# femtoBeacon_PRO_r3_0_2_single_sided.net
KiCad netlist of a schematic drawn in EAGLE
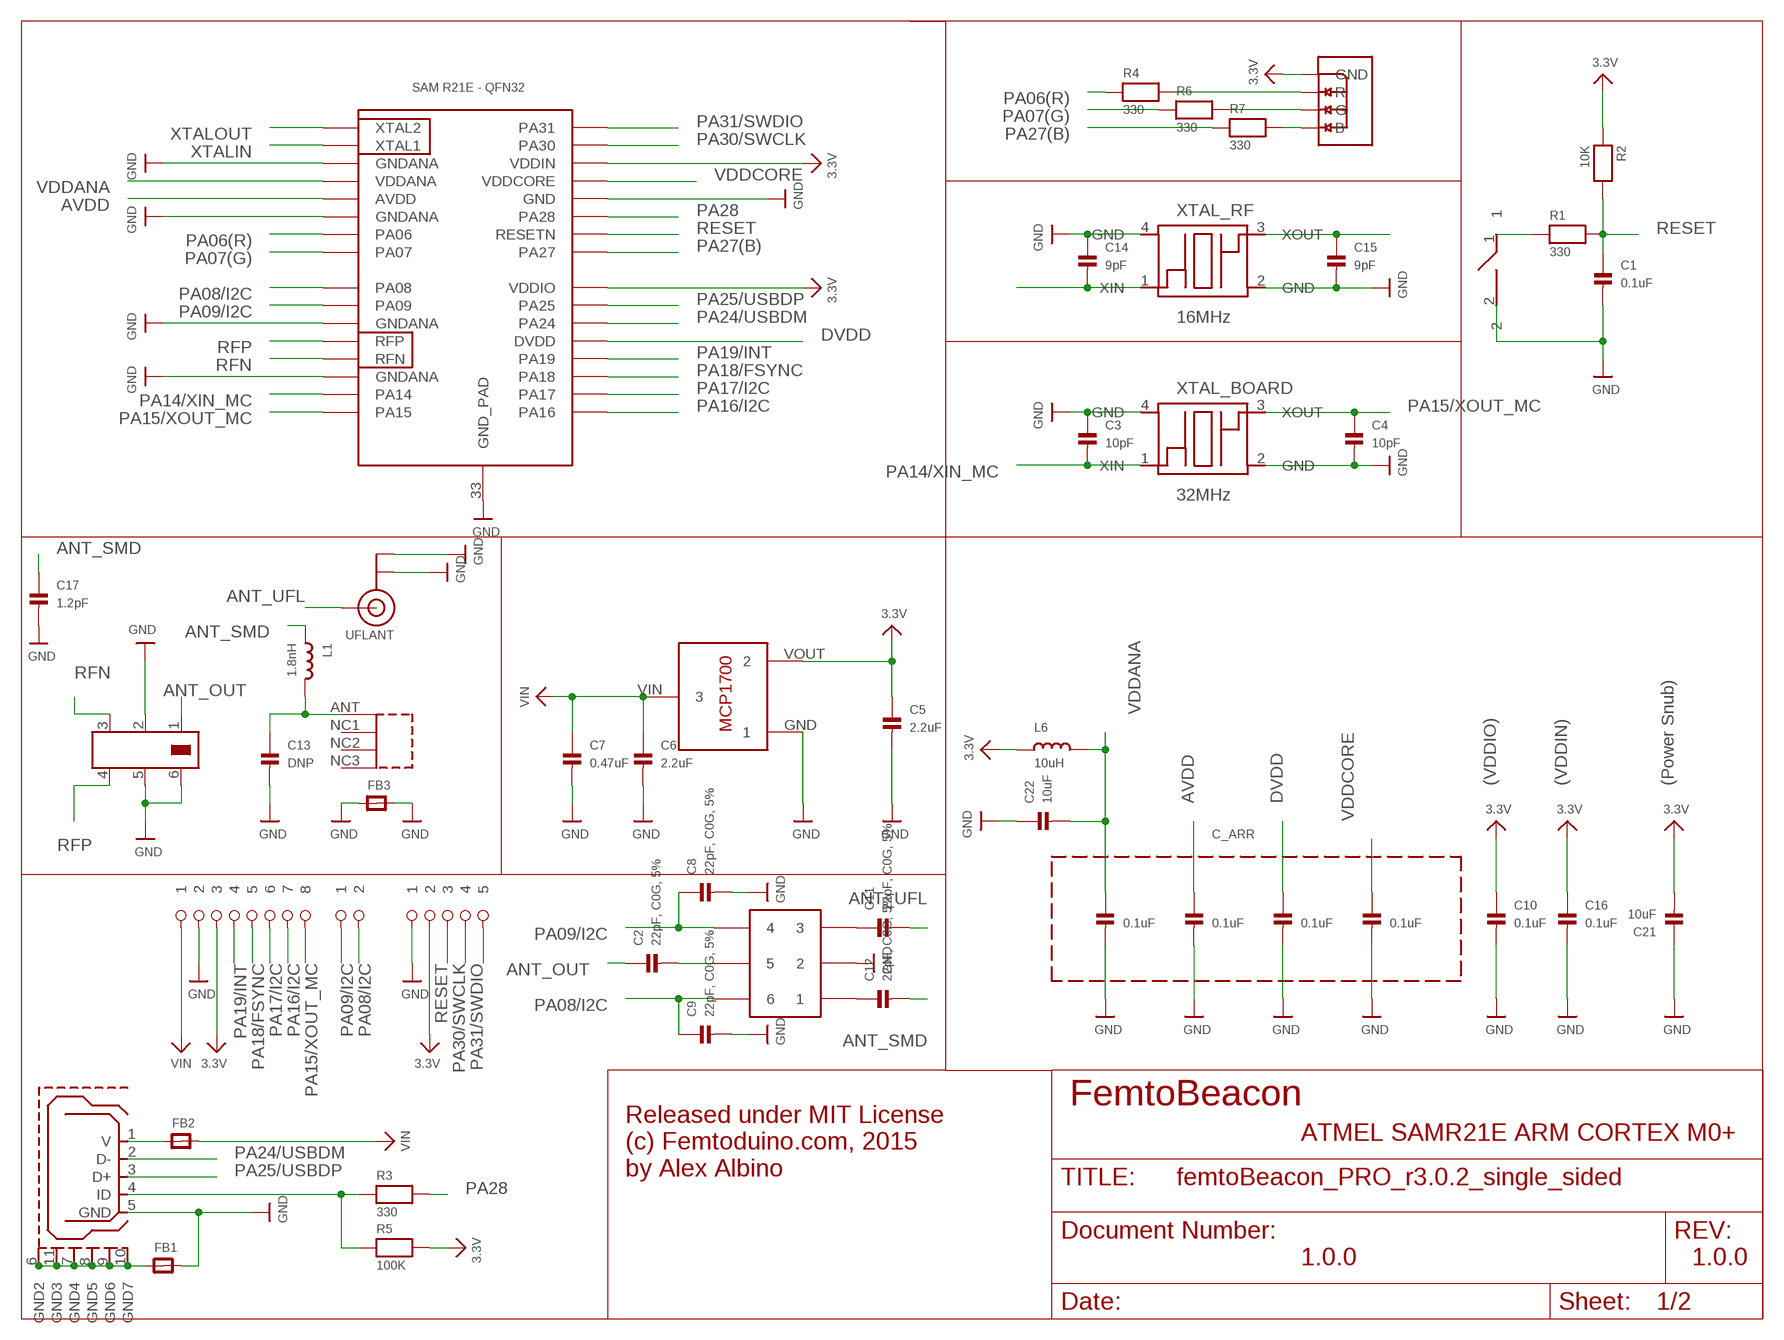
[diagram p0: schematic, sheet 1]
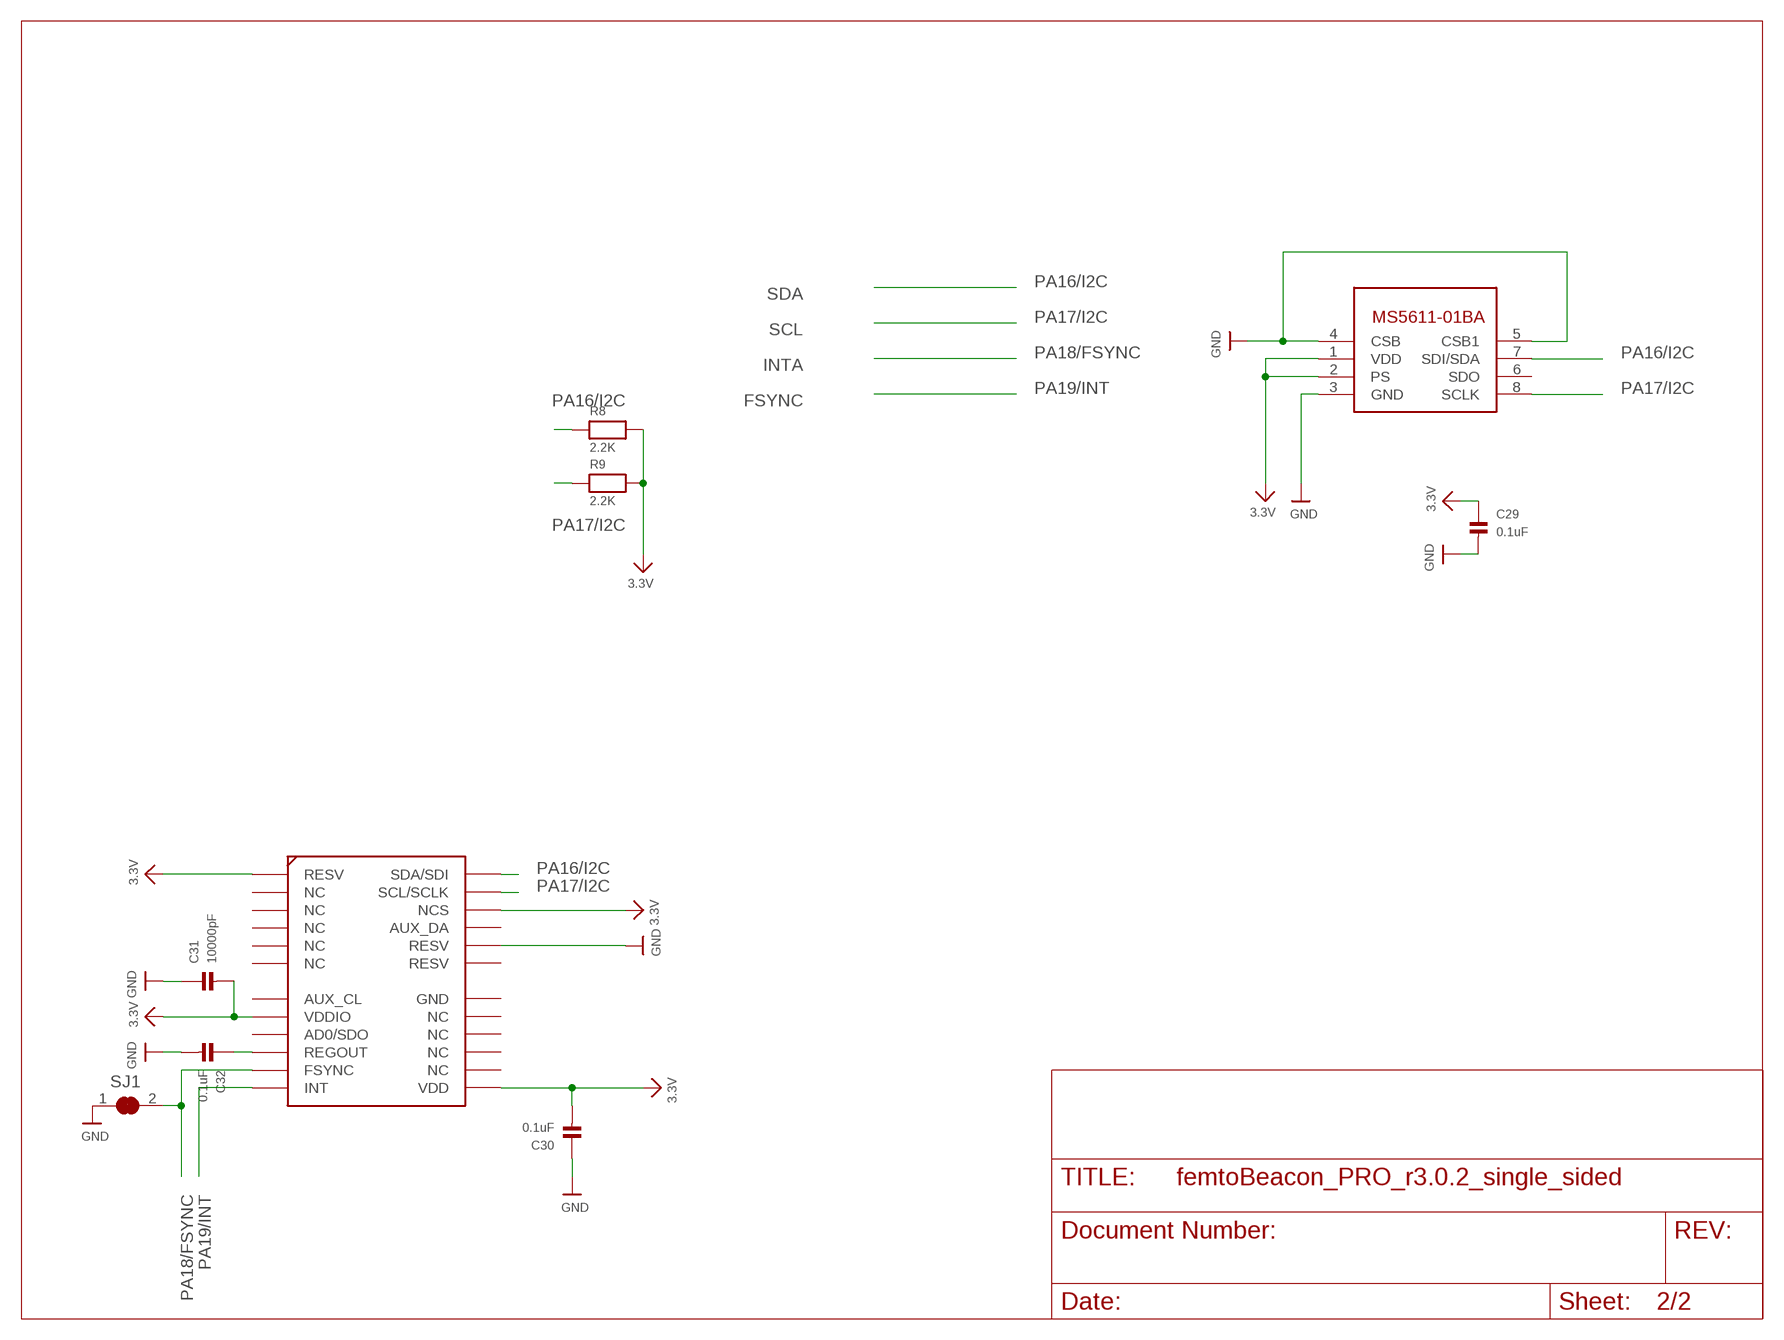
[diagram p1: schematic, sheet 2]

(export (version "E")
  (design (tool "Eeschema 10.0.6"))
  (components
    (comp (ref "ASWITCH")
      (value "AS222-92LF")
      (footprint "eagle-import:AS222-92LF")
      (libsource (lib "eagle-import") (part "AS222-92LF"))
    )
    (comp (ref "BALUN")
      (value "JOHANSON_2450BM15A0015E")
      (footprint "eagle-import:0805_BALUN")
      (libsource (lib "eagle-import") (part "JOHANSON_2450BM15A0015E"))
    )
    (comp (ref "BTN_RESET")
      (value "DNP")
      (footprint "eagle-import:SPST_SMD")
      (libsource (lib "eagle-import") (part "SPST_SMD"))
    )
    (comp (ref "C1")
      (value "0.1uF")
      (footprint "eagle-import:_0402MP")
      (fields (field (name "DIGIKEY_PART") "490-3194-1-ND"))
      (libsource (lib "eagle-import") (part "CAP_CERAMIC_0402MP"))
    )
    (comp (ref "C2")
      (value "22pF, C0G, 5%")
      (footprint "eagle-import:_0402MP")
      (fields (field (name "DIGIKEY_PART") "490-3194-1-ND"))
      (libsource (lib "eagle-import") (part "CAP_CERAMIC_0402MP"))
    )
    (comp (ref "C3")
      (value "10pF")
      (footprint "eagle-import:_0402MP")
      (fields (field (name "DIGIKEY_PART") "490-3194-1-ND"))
      (libsource (lib "eagle-import") (part "CAP_CERAMIC_0402MP"))
    )
    (comp (ref "C4")
      (value "10pF")
      (footprint "eagle-import:_0402MP")
      (fields (field (name "DIGIKEY_PART") "490-3194-1-ND"))
      (libsource (lib "eagle-import") (part "CAP_CERAMIC_0402MP"))
    )
    (comp (ref "C5")
      (value "2.2uF")
      (footprint "eagle-import:_0402MP")
      (libsource (lib "eagle-import") (part "CAP_CERAMIC_0402MP"))
    )
    (comp (ref "C6")
      (value "2.2uF")
      (footprint "eagle-import:_0402MP")
      (libsource (lib "eagle-import") (part "CAP_CERAMIC_0402MP"))
    )
    (comp (ref "C7")
      (value "0.47uF")
      (footprint "eagle-import:_0402MP")
      (libsource (lib "eagle-import") (part "CAP_CERAMIC_0402MP"))
    )
    (comp (ref "C8")
      (value "22pF, C0G, 5%")
      (footprint "eagle-import:_0402MP")
      (fields (field (name "DIGIKEY_PART") "490-3194-1-ND"))
      (libsource (lib "eagle-import") (part "CAP_CERAMIC_0402MP"))
    )
    (comp (ref "C9")
      (value "22pF, C0G, 5%")
      (footprint "eagle-import:_0402MP")
      (fields (field (name "DIGIKEY_PART") "490-3194-1-ND"))
      (libsource (lib "eagle-import") (part "CAP_CERAMIC_0402MP"))
    )
    (comp (ref "C10")
      (value "0.1uF")
      (footprint "eagle-import:_0402MP")
      (fields (field (name "DIGIKEY_PART") "490-3194-1-ND"))
      (libsource (lib "eagle-import") (part "CAP_CERAMIC_0402MP"))
    )
    (comp (ref "C11")
      (value "22pF, C0G, 5%")
      (footprint "eagle-import:_0402MP")
      (fields (field (name "DIGIKEY_PART") "490-3194-1-ND"))
      (libsource (lib "eagle-import") (part "CAP_CERAMIC_0402MP"))
    )
    (comp (ref "C12")
      (value "22pF, C0G, 5%")
      (footprint "eagle-import:_0402MP")
      (fields (field (name "DIGIKEY_PART") "490-3194-1-ND"))
      (libsource (lib "eagle-import") (part "CAP_CERAMIC_0402MP"))
    )
    (comp (ref "C13")
      (value "DNP")
      (footprint "eagle-import:_0402MP")
      (fields (field (name "DIGIKEY_PART") "490-3194-1-ND"))
      (libsource (lib "eagle-import") (part "CAP_CERAMIC_0402MP"))
    )
    (comp (ref "C14")
      (value "9pF")
      (footprint "eagle-import:_0402MP")
      (fields (field (name "DIGIKEY_PART") "490-3194-1-ND"))
      (libsource (lib "eagle-import") (part "CAP_CERAMIC_0402MP"))
    )
    (comp (ref "C15")
      (value "9pF")
      (footprint "eagle-import:_0402MP")
      (fields (field (name "DIGIKEY_PART") "490-3194-1-ND"))
      (libsource (lib "eagle-import") (part "CAP_CERAMIC_0402MP"))
    )
    (comp (ref "C16")
      (value "0.1uF")
      (footprint "eagle-import:_0402MP")
      (fields (field (name "DIGIKEY_PART") "490-3194-1-ND"))
      (libsource (lib "eagle-import") (part "CAP_CERAMIC_0402MP"))
    )
    (comp (ref "C17")
      (value "1.2pF")
      (footprint "eagle-import:_0402MP")
      (libsource (lib "eagle-import") (part "CAP_CERAMIC_0402MP"))
    )
    (comp (ref "C21")
      (value "10uF")
      (footprint "eagle-import:_0402MP")
      (libsource (lib "eagle-import") (part "CAP_CERAMIC_0402MP"))
    )
    (comp (ref "C22")
      (value "10uF")
      (footprint "eagle-import:_0402MP")
      (libsource (lib "eagle-import") (part "CAP_CERAMIC_0402MP"))
    )
    (comp (ref "C_ARR")
      (value "0.1uF")
      (footprint "eagle-import:CAPACITOR_ARRAY_1206_MONO_1X4")
      (libsource (lib "eagle-import") (part "KEMET_CERAMIC_CAPACITOR_ARRAY_1X4"))
    )
    (comp (ref "FB1")
      (value "FERRITE_0603MP")
      (footprint "eagle-import:_0603MP")
      (libsource (lib "eagle-import") (part "FERRITE_0603MP"))
    )
    (comp (ref "FB2")
      (value "FERRITE_0603MP")
      (footprint "eagle-import:_0603MP")
      (libsource (lib "eagle-import") (part "FERRITE_0603MP"))
    )
    (comp (ref "FB3")
      (value "FERRITE_0603MP")
      (footprint "eagle-import:_0603MP")
      (libsource (lib "eagle-import") (part "FERRITE_0603MP"))
    )
    (comp (ref "IC")
      (value "ATSAMR21E18A-MUT")
      (footprint "eagle-import:QFN32")
      (libsource (lib "eagle-import") (part "ATSAMR21E18A-MUT"))
    )
    (comp (ref "L1")
      (value "1.8nH")
      (footprint "eagle-import:_0603MP")
      (libsource (lib "eagle-import") (part "INDUCTOR_0603MP"))
    )
    (comp (ref "L6")
      (value "10uH")
      (footprint "eagle-import:_0603MP")
      (libsource (lib "eagle-import") (part "INDUCTOR_0603MP"))
    )
    (comp (ref "LDO_VREG")
      (value "MCP1700T-3302E/TT")
      (footprint "eagle-import:MCP1700T-3302E_TT")
      (libsource (lib "eagle-import") (part "MCP1700T-3302E/TT"))
    )
    (comp (ref "R1")
      (value "330")
      (footprint "eagle-import:_0402MP")
      (libsource (lib "eagle-import") (part "RESISTOR_0402MP"))
    )
    (comp (ref "R2")
      (value "10K")
      (footprint "eagle-import:_0402MP")
      (libsource (lib "eagle-import") (part "RESISTOR_0402MP"))
    )
    (comp (ref "R3")
      (value "330")
      (footprint "eagle-import:_0402MP")
      (libsource (lib "eagle-import") (part "RESISTOR_0402MP"))
    )
    (comp (ref "R4")
      (value "330")
      (footprint "eagle-import:_0402MP")
      (libsource (lib "eagle-import") (part "RESISTOR_0402MP"))
    )
    (comp (ref "R5")
      (value "100K")
      (footprint "eagle-import:_0402MP")
      (libsource (lib "eagle-import") (part "RESISTOR_0402MP"))
    )
    (comp (ref "R6")
      (value "330")
      (footprint "eagle-import:_0402MP")
      (libsource (lib "eagle-import") (part "RESISTOR_0402MP"))
    )
    (comp (ref "R7")
      (value "330")
      (footprint "eagle-import:_0402MP")
      (libsource (lib "eagle-import") (part "RESISTOR_0402MP"))
    )
    (comp (ref "RGBLED")
      (value "LRTB_R48G")
      (footprint "eagle-import:LRTB_R48G")
      (libsource (lib "eagle-import") (part "LRTB_R48G"))
    )
    (comp (ref "U$5")
      (value "1X8_ROUND")
      (footprint "eagle-import:1X8_ROUND")
      (libsource (lib "eagle-import") (part "1X8_ROUND"))
    )
    (comp (ref "U$9")
      (value "1X2_ROUND")
      (footprint "eagle-import:1X2_ROUND")
      (libsource (lib "eagle-import") (part "1X2_ROUND"))
    )
    (comp (ref "U$10")
      (value "1X5_ROUND")
      (footprint "eagle-import:1X5_ROUND")
      (libsource (lib "eagle-import") (part "1X5_ROUND"))
    )
    (comp (ref "U$12")
      (value "0479480001")
      (footprint "eagle-import:0479480001")
      (libsource (lib "eagle-import") (part "0479480001"))
    )
    (comp (ref "UFLANT")
      (value "ANTENNA_U.FL")
      (footprint "eagle-import:U.FL")
      (libsource (lib "eagle-import") (part "ANTENNA_U.FL"))
    )
    (comp (ref "USB")
      (value "USB_MICROB")
      (footprint "eagle-import:USB_MICROB_PACKAGE")
      (libsource (lib "eagle-import") (part "USB_MICROB"))
    )
    (comp (ref "XTAL_BOARD")
      (value "32MHz")
      (footprint "eagle-import:FA-128")
      (libsource (lib "eagle-import") (part "FA-128"))
    )
    (comp (ref "XTAL_RF")
      (value "16MHz")
      (footprint "eagle-import:TSX-3225")
      (libsource (lib "eagle-import") (part "TSX-3225"))
    )
    (comp (ref "BARO")
      (value "MS5611-01BA03")
      (footprint "eagle-import:MS5611-01BA03")
      (libsource (lib "eagle-import") (part "MS5611-01BA03"))
    )
    (comp (ref "C29")
      (value "0.1uF")
      (footprint "eagle-import:_0402MP")
      (fields (field (name "DIGIKEY_PART") "490-3194-1-ND"))
      (libsource (lib "eagle-import") (part "CAP_CERAMIC_0402MP"))
    )
    (comp (ref "C30")
      (value "0.1uF")
      (footprint "eagle-import:_0402MP")
      (fields (field (name "DIGIKEY_PART") "490-3194-1-ND"))
      (libsource (lib "eagle-import") (part "CAP_CERAMIC_0402MP"))
    )
    (comp (ref "C31")
      (value "10000pF")
      (footprint "eagle-import:_0402MP")
      (fields (field (name "DIGIKEY_PART") "490-3194-1-ND"))
      (libsource (lib "eagle-import") (part "CAP_CERAMIC_0402MP"))
    )
    (comp (ref "C32")
      (value "0.1uF")
      (footprint "eagle-import:_0402MP")
      (fields (field (name "DIGIKEY_PART") "490-3194-1-ND"))
      (libsource (lib "eagle-import") (part "CAP_CERAMIC_0402MP"))
    )
    (comp (ref "IMU")
      (value "MPU-9250")
      (footprint "eagle-import:QFN_3X3MM")
      (libsource (lib "eagle-import") (part "MPU-9250"))
    )
    (comp (ref "R8")
      (value "2.2K")
      (footprint "eagle-import:_0402MP")
      (libsource (lib "eagle-import") (part "RESISTOR_0402MP"))
    )
    (comp (ref "R9")
      (value "2.2K")
      (footprint "eagle-import:_0402MP")
      (libsource (lib "eagle-import") (part "RESISTOR_0402MP"))
    )
    (comp (ref "SJ1")
      (value "SOLDERJUMPER_CLOSED")
      (footprint "eagle-import:SOLDERJUMPER_CLOSEDWIRE")
      (libsource (lib "eagle-import") (part "SOLDERJUMPER_CLOSED"))
    )
  )
  (nets
    (net (code "1") (name "3.3V") (class "Default")
      (node (ref "BARO") (pin "1") (pinfunction "VDD_1") (pintype "bidirectional"))
      (node (ref "BARO") (pin "2") (pinfunction "PS_2") (pintype "bidirectional"))
      (node (ref "C10") (pin "1") (pinfunction "P$1_1") (pintype "passive"))
      (node (ref "C16") (pin "1") (pinfunction "P$1_1") (pintype "passive"))
      (node (ref "C21") (pin "2") (pinfunction "P$2_2") (pintype "passive"))
      (node (ref "C29") (pin "1") (pinfunction "P$1_1") (pintype "passive"))
      (node (ref "C30") (pin "2") (pinfunction "P$2_2") (pintype "passive"))
      (node (ref "C31") (pin "2") (pinfunction "P$2_2") (pintype "passive"))
      (node (ref "C5") (pin "1") (pinfunction "P$1_1") (pintype "passive"))
      (node (ref "IC") (pin "24") (pinfunction "VDDIO_24") (pintype "bidirectional"))
      (node (ref "IC") (pin "30") (pinfunction "VDDIN_30") (pintype "bidirectional"))
      (node (ref "IMU") (pin "P$1") (pinfunction "RESV_P$1") (pintype "bidirectional"))
      (node (ref "IMU") (pin "P$13") (pinfunction "VDD_P$13") (pintype "bidirectional"))
      (node (ref "IMU") (pin "P$22") (pinfunction "NCS_P$22") (pintype "bidirectional"))
      (node (ref "IMU") (pin "P$8") (pinfunction "VDDIO_P$8") (pintype "bidirectional"))
      (node (ref "L6") (pin "1") (pinfunction "1_1") (pintype "passive"))
      (node (ref "LDO_VREG") (pin "VOUT") (pinfunction "2_VOUT") (pintype "bidirectional"))
      (node (ref "R2") (pin "1") (pinfunction "1_1") (pintype "passive"))
      (node (ref "R5") (pin "2") (pinfunction "2_2") (pintype "passive"))
      (node (ref "R8") (pin "2") (pinfunction "2_2") (pintype "passive"))
      (node (ref "R9") (pin "2") (pinfunction "2_2") (pintype "passive"))
      (node (ref "RGBLED") (pin "1") (pinfunction "GND_1") (pintype "bidirectional"))
      (node (ref "U$10") (pin "P$2") (pinfunction "2_P$2") (pintype "bidirectional"))
      (node (ref "U$5") (pin "P$3") (pinfunction "3_P$3") (pintype "bidirectional"))
    )
    (net (code "2") (name "ANT_OUT") (class "Default")
      (node (ref "BALUN") (pin "1") (pinfunction "1_1") (pintype "bidirectional"))
      (node (ref "C2") (pin "1") (pinfunction "P$1_1") (pintype "passive"))
    )
    (net (code "3") (name "ANT_SMD") (class "Default")
      (node (ref "C12") (pin "2") (pinfunction "P$2_2") (pintype "passive"))
      (node (ref "C17") (pin "1") (pinfunction "P$1_1") (pintype "passive"))
      (node (ref "L1") (pin "1") (pinfunction "1_1") (pintype "passive"))
    )
    (net (code "4") (name "ANT_UFL") (class "Default")
      (node (ref "C11") (pin "2") (pinfunction "P$2_2") (pintype "passive"))
      (node (ref "UFLANT") (pin "3") (pinfunction "SIGNAL_3") (pintype "passive"))
    )
    (net (code "5") (name "AVDD") (class "Default")
      (node (ref "C_ARR") (pin "3") (pinfunction "P$3_3") (pintype "passive"))
      (node (ref "IC") (pin "5") (pinfunction "AVDD_5") (pintype "bidirectional"))
    )
    (net (code "6") (name "DVDD") (class "Default")
      (node (ref "C_ARR") (pin "5") (pinfunction "P$5_5") (pintype "passive"))
      (node (ref "IC") (pin "21") (pinfunction "DVDD_21") (pintype "bidirectional"))
    )
    (net (code "7") (name "GND") (class "Default")
      (node (ref "ASWITCH") (pin "PIN2") (pinfunction "2_PIN2") (pintype "bidirectional"))
      (node (ref "BALUN") (pin "2") (pinfunction "2_2") (pintype "bidirectional"))
      (node (ref "BALUN") (pin "5") (pinfunction "5_5") (pintype "bidirectional"))
      (node (ref "BALUN") (pin "6") (pinfunction "6_6") (pintype "bidirectional"))
      (node (ref "BARO") (pin "3") (pinfunction "GND_3") (pintype "bidirectional"))
      (node (ref "BARO") (pin "4") (pinfunction "CSB_4") (pintype "bidirectional"))
      (node (ref "BARO") (pin "5") (pinfunction "CSB1_5") (pintype "bidirectional"))
      (node (ref "BTN_RESET") (pin "2") (pinfunction "2_2") (pintype "bidirectional"))
      (node (ref "C1") (pin "2") (pinfunction "P$2_2") (pintype "passive"))
      (node (ref "C10") (pin "2") (pinfunction "P$2_2") (pintype "passive"))
      (node (ref "C13") (pin "2") (pinfunction "P$2_2") (pintype "passive"))
      (node (ref "C14") (pin "1") (pinfunction "P$1_1") (pintype "passive"))
      (node (ref "C15") (pin "2") (pinfunction "P$2_2") (pintype "passive"))
      (node (ref "C16") (pin "2") (pinfunction "P$2_2") (pintype "passive"))
      (node (ref "C17") (pin "2") (pinfunction "P$2_2") (pintype "passive"))
      (node (ref "C21") (pin "1") (pinfunction "P$1_1") (pintype "passive"))
      (node (ref "C22") (pin "1") (pinfunction "P$1_1") (pintype "passive"))
      (node (ref "C29") (pin "2") (pinfunction "P$2_2") (pintype "passive"))
      (node (ref "C3") (pin "1") (pinfunction "P$1_1") (pintype "passive"))
      (node (ref "C30") (pin "1") (pinfunction "P$1_1") (pintype "passive"))
      (node (ref "C31") (pin "1") (pinfunction "P$1_1") (pintype "passive"))
      (node (ref "C32") (pin "2") (pinfunction "P$2_2") (pintype "passive"))
      (node (ref "C4") (pin "2") (pinfunction "P$2_2") (pintype "passive"))
      (node (ref "C5") (pin "2") (pinfunction "P$2_2") (pintype "passive"))
      (node (ref "C6") (pin "2") (pinfunction "P$2_2") (pintype "passive"))
      (node (ref "C7") (pin "2") (pinfunction "P$2_2") (pintype "passive"))
      (node (ref "C8") (pin "2") (pinfunction "P$2_2") (pintype "passive"))
      (node (ref "C9") (pin "2") (pinfunction "P$2_2") (pintype "passive"))
      (node (ref "C_ARR") (pin "2") (pinfunction "P$2_2") (pintype "passive"))
      (node (ref "C_ARR") (pin "4") (pinfunction "P$4_4") (pintype "passive"))
      (node (ref "C_ARR") (pin "6") (pinfunction "P$6_6") (pintype "passive"))
      (node (ref "C_ARR") (pin "8") (pinfunction "P$8_8") (pintype "passive"))
      (node (ref "FB1") (pin "2") (pinfunction "P$2_2") (pintype "passive"))
      (node (ref "FB3") (pin "1") (pinfunction "P$1_1") (pintype "passive"))
      (node (ref "FB3") (pin "2") (pinfunction "P$2_2") (pintype "passive"))
      (node (ref "IC") (pin "11") (pinfunction "GNDANA_11") (pintype "bidirectional"))
      (node (ref "IC") (pin "14") (pinfunction "GNDANA_14") (pintype "bidirectional"))
      (node (ref "IC") (pin "28") (pinfunction "GND_28") (pintype "bidirectional"))
      (node (ref "IC") (pin "3") (pinfunction "GNDANA_3") (pintype "bidirectional"))
      (node (ref "IC") (pin "33") (pinfunction "GND_PAD_33") (pintype "bidirectional"))
      (node (ref "IC") (pin "6") (pinfunction "GNDANA_6") (pintype "bidirectional"))
      (node (ref "IMU") (pin "P$20") (pinfunction "RESV_P$20") (pintype "bidirectional"))
      (node (ref "LDO_VREG") (pin "GND") (pinfunction "1_GND") (pintype "bidirectional"))
      (node (ref "SJ1") (pin "1") (pinfunction "1_1") (pintype "passive"))
      (node (ref "U$10") (pin "P$1") (pinfunction "1_P$1") (pintype "bidirectional"))
      (node (ref "U$5") (pin "P$2") (pinfunction "2_P$2") (pintype "bidirectional"))
      (node (ref "UFLANT") (pin "1") (pinfunction "GND_1") (pintype "passive"))
      (node (ref "UFLANT") (pin "2") (pinfunction "GND_2") (pintype "passive"))
      (node (ref "USB") (pin "5") (pinfunction "GND_5") (pintype "bidirectional"))
      (node (ref "XTAL_BOARD") (pin "2") (pinfunction "GND_2") (pintype "bidirectional"))
      (node (ref "XTAL_BOARD") (pin "4") (pinfunction "GND_4") (pintype "bidirectional"))
      (node (ref "XTAL_RF") (pin "2") (pinfunction "GND_2") (pintype "bidirectional"))
      (node (ref "XTAL_RF") (pin "4") (pinfunction "GND_4") (pintype "bidirectional"))
    )
    (net (code "8") (name "Net-(ASWITCH-1)") (class "Default")
      (node (ref "ASWITCH") (pin "PIN1") (pinfunction "1_PIN1") (pintype "bidirectional"))
      (node (ref "C12") (pin "1") (pinfunction "P$1_1") (pintype "passive"))
    )
    (net (code "9") (name "Net-(ASWITCH-3)") (class "Default")
      (node (ref "ASWITCH") (pin "PIN3") (pinfunction "3_PIN3") (pintype "bidirectional"))
      (node (ref "C11") (pin "1") (pinfunction "P$1_1") (pintype "passive"))
    )
    (net (code "10") (name "Net-(ASWITCH-5)") (class "Default")
      (node (ref "ASWITCH") (pin "PIN5") (pinfunction "5_PIN5") (pintype "bidirectional"))
      (node (ref "C2") (pin "2") (pinfunction "P$2_2") (pintype "passive"))
    )
    (net (code "11") (name "Net-(BTN_RESET-Pad1)") (class "Default")
      (node (ref "BTN_RESET") (pin "1") (pinfunction "1_1") (pintype "bidirectional"))
      (node (ref "R1") (pin "1") (pinfunction "1_1") (pintype "passive"))
    )
    (net (code "12") (name "Net-(C13-P$1)") (class "Default")
      (node (ref "C13") (pin "1") (pinfunction "P$1_1") (pintype "passive"))
      (node (ref "L1") (pin "2") (pinfunction "2_2") (pintype "passive"))
      (node (ref "U$12") (pin "ANT") (pinfunction "1_ANT") (pintype "bidirectional"))
    )
    (net (code "13") (name "Net-(C32-P$1)") (class "Default")
      (node (ref "C32") (pin "1") (pinfunction "P$1_1") (pintype "passive"))
      (node (ref "IMU") (pin "P$10") (pinfunction "REGOUT_P$10") (pintype "bidirectional"))
    )
    (net (code "14") (name "Net-(FB1-P$1)") (class "Default")
      (node (ref "FB1") (pin "1") (pinfunction "P$1_1") (pintype "passive"))
      (node (ref "USB") (pin "10") (pinfunction "GND7_10") (pintype "bidirectional"))
      (node (ref "USB") (pin "11") (pinfunction "GND3_11") (pintype "bidirectional"))
      (node (ref "USB") (pin "6") (pinfunction "GND2_6") (pintype "bidirectional"))
      (node (ref "USB") (pin "7") (pinfunction "GND4_7") (pintype "bidirectional"))
      (node (ref "USB") (pin "8") (pinfunction "GND5_8") (pintype "bidirectional"))
      (node (ref "USB") (pin "9") (pinfunction "GND6_9") (pintype "bidirectional"))
    )
    (net (code "15") (name "Net-(FB2-P$1)") (class "Default")
      (node (ref "FB2") (pin "1") (pinfunction "P$1_1") (pintype "passive"))
      (node (ref "USB") (pin "1") (pinfunction "V_1") (pintype "bidirectional"))
    )
    (net (code "16") (name "Net-(RGBLED-B)") (class "Default")
      (node (ref "R7") (pin "2") (pinfunction "2_2") (pintype "passive"))
      (node (ref "RGBLED") (pin "4") (pinfunction "B_4") (pintype "bidirectional"))
    )
    (net (code "17") (name "Net-(RGBLED-G)") (class "Default")
      (node (ref "R6") (pin "2") (pinfunction "2_2") (pintype "passive"))
      (node (ref "RGBLED") (pin "3") (pinfunction "G_3") (pintype "bidirectional"))
    )
    (net (code "18") (name "Net-(RGBLED-R)") (class "Default")
      (node (ref "R4") (pin "2") (pinfunction "2_2") (pintype "passive"))
      (node (ref "RGBLED") (pin "2") (pinfunction "R_2") (pintype "bidirectional"))
    )
    (net (code "19") (name "Net-(USB-ID)") (class "Default")
      (node (ref "R3") (pin "1") (pinfunction "1_1") (pintype "passive"))
      (node (ref "R5") (pin "1") (pinfunction "1_1") (pintype "passive"))
      (node (ref "USB") (pin "4") (pinfunction "ID_4") (pintype "bidirectional"))
    )
    (net (code "20") (name "PA06(R)") (class "Default")
      (node (ref "IC") (pin "7") (pinfunction "PA06_7") (pintype "bidirectional"))
      (node (ref "R4") (pin "1") (pinfunction "1_1") (pintype "passive"))
    )
    (net (code "21") (name "PA07(G)") (class "Default")
      (node (ref "IC") (pin "8") (pinfunction "PA07_8") (pintype "bidirectional"))
      (node (ref "R6") (pin "1") (pinfunction "1_1") (pintype "passive"))
    )
    (net (code "22") (name "PA08{slash}I2C") (class "Default")
      (node (ref "ASWITCH") (pin "PIN6") (pinfunction "6_PIN6") (pintype "bidirectional"))
      (node (ref "C9") (pin "1") (pinfunction "P$1_1") (pintype "passive"))
      (node (ref "IC") (pin "9") (pinfunction "PA08_9") (pintype "bidirectional"))
      (node (ref "U$9") (pin "P$2") (pinfunction "2_P$2") (pintype "bidirectional"))
    )
    (net (code "23") (name "PA09{slash}I2C") (class "Default")
      (node (ref "ASWITCH") (pin "PIN4") (pinfunction "4_PIN4") (pintype "bidirectional"))
      (node (ref "C8") (pin "1") (pinfunction "P$1_1") (pintype "passive"))
      (node (ref "IC") (pin "10") (pinfunction "PA09_10") (pintype "bidirectional"))
      (node (ref "U$9") (pin "P$1") (pinfunction "1_P$1") (pintype "bidirectional"))
    )
    (net (code "24") (name "PA14{slash}XIN_MC") (class "Default")
      (node (ref "C3") (pin "2") (pinfunction "P$2_2") (pintype "passive"))
      (node (ref "IC") (pin "15") (pinfunction "PA14_15") (pintype "bidirectional"))
      (node (ref "XTAL_BOARD") (pin "1") (pinfunction "XIN_1") (pintype "bidirectional"))
    )
    (net (code "25") (name "PA15{slash}XOUT_MC") (class "Default")
      (node (ref "C4") (pin "1") (pinfunction "P$1_1") (pintype "passive"))
      (node (ref "IC") (pin "16") (pinfunction "PA15_16") (pintype "bidirectional"))
      (node (ref "U$5") (pin "P$8") (pinfunction "8_P$8") (pintype "bidirectional"))
      (node (ref "XTAL_BOARD") (pin "3") (pinfunction "XOUT_3") (pintype "bidirectional"))
    )
    (net (code "26") (name "PA16{slash}I2C") (class "Default")
      (node (ref "BARO") (pin "7") (pinfunction "SDI/SDA_7") (pintype "bidirectional"))
      (node (ref "IC") (pin "17") (pinfunction "PA16_17") (pintype "bidirectional"))
      (node (ref "IMU") (pin "P$24") (pinfunction "SDA/SDI_P$24") (pintype "bidirectional"))
      (node (ref "R8") (pin "1") (pinfunction "1_1") (pintype "passive"))
      (node (ref "U$5") (pin "P$7") (pinfunction "7_P$7") (pintype "bidirectional"))
    )
    (net (code "27") (name "PA17{slash}I2C") (class "Default")
      (node (ref "BARO") (pin "8") (pinfunction "SCLK_8") (pintype "bidirectional"))
      (node (ref "IC") (pin "18") (pinfunction "PA17_18") (pintype "bidirectional"))
      (node (ref "IMU") (pin "P$23") (pinfunction "SCL/SCLK_P$23") (pintype "bidirectional"))
      (node (ref "R9") (pin "1") (pinfunction "1_1") (pintype "passive"))
      (node (ref "U$5") (pin "P$6") (pinfunction "6_P$6") (pintype "bidirectional"))
    )
    (net (code "28") (name "PA18{slash}FSYNC") (class "Default")
      (node (ref "IC") (pin "19") (pinfunction "PA18_19") (pintype "bidirectional"))
      (node (ref "IMU") (pin "P$11") (pinfunction "FSYNC_P$11") (pintype "bidirectional"))
      (node (ref "SJ1") (pin "2") (pinfunction "2_2") (pintype "passive"))
      (node (ref "U$5") (pin "P$5") (pinfunction "5_P$5") (pintype "bidirectional"))
    )
    (net (code "29") (name "PA19{slash}INT") (class "Default")
      (node (ref "IC") (pin "20") (pinfunction "PA19_20") (pintype "bidirectional"))
      (node (ref "IMU") (pin "P$12") (pinfunction "INT_P$12") (pintype "bidirectional"))
      (node (ref "U$5") (pin "P$4") (pinfunction "4_P$4") (pintype "bidirectional"))
    )
    (net (code "30") (name "PA24{slash}USBDM") (class "Default")
      (node (ref "IC") (pin "22") (pinfunction "PA24_22") (pintype "bidirectional"))
      (node (ref "USB") (pin "2") (pinfunction "D-_2") (pintype "bidirectional"))
    )
    (net (code "31") (name "PA25{slash}USBDP") (class "Default")
      (node (ref "IC") (pin "23") (pinfunction "PA25_23") (pintype "bidirectional"))
      (node (ref "USB") (pin "3") (pinfunction "D+_3") (pintype "bidirectional"))
    )
    (net (code "32") (name "PA27(B)") (class "Default")
      (node (ref "IC") (pin "25") (pinfunction "PA27_25") (pintype "bidirectional"))
      (node (ref "R7") (pin "1") (pinfunction "1_1") (pintype "passive"))
    )
    (net (code "33") (name "PA28") (class "Default")
      (node (ref "IC") (pin "27") (pinfunction "PA28_27") (pintype "bidirectional"))
      (node (ref "R3") (pin "2") (pinfunction "2_2") (pintype "passive"))
    )
    (net (code "34") (name "PA30{slash}SWCLK") (class "Default")
      (node (ref "IC") (pin "31") (pinfunction "PA30_31") (pintype "bidirectional"))
      (node (ref "U$10") (pin "P$4") (pinfunction "4_P$4") (pintype "bidirectional"))
    )
    (net (code "35") (name "PA31{slash}SWDIO") (class "Default")
      (node (ref "IC") (pin "32") (pinfunction "PA31_32") (pintype "bidirectional"))
      (node (ref "U$10") (pin "P$5") (pinfunction "5_P$5") (pintype "bidirectional"))
    )
    (net (code "36") (name "RESET") (class "Default")
      (node (ref "C1") (pin "1") (pinfunction "P$1_1") (pintype "passive"))
      (node (ref "IC") (pin "26") (pinfunction "RESETN_26") (pintype "bidirectional"))
      (node (ref "R1") (pin "2") (pinfunction "2_2") (pintype "passive"))
      (node (ref "R2") (pin "2") (pinfunction "2_2") (pintype "passive"))
      (node (ref "U$10") (pin "P$3") (pinfunction "3_P$3") (pintype "bidirectional"))
    )
    (net (code "37") (name "RFN") (class "Default")
      (node (ref "BALUN") (pin "3") (pinfunction "3_3") (pintype "bidirectional"))
      (node (ref "IC") (pin "13") (pinfunction "RFN_13") (pintype "bidirectional"))
    )
    (net (code "38") (name "RFP") (class "Default")
      (node (ref "BALUN") (pin "4") (pinfunction "4_4") (pintype "bidirectional"))
      (node (ref "IC") (pin "12") (pinfunction "RFP_12") (pintype "bidirectional"))
    )
    (net (code "39") (name "VDDANA") (class "Default")
      (node (ref "C22") (pin "2") (pinfunction "P$2_2") (pintype "passive"))
      (node (ref "C_ARR") (pin "1") (pinfunction "P$1_1") (pintype "passive"))
      (node (ref "IC") (pin "4") (pinfunction "VDDANA_4") (pintype "bidirectional"))
      (node (ref "L6") (pin "2") (pinfunction "2_2") (pintype "passive"))
    )
    (net (code "40") (name "VDDCORE") (class "Default")
      (node (ref "C_ARR") (pin "7") (pinfunction "P$7_7") (pintype "passive"))
      (node (ref "IC") (pin "29") (pinfunction "VDDCORE_29") (pintype "bidirectional"))
    )
    (net (code "41") (name "VIN") (class "Default")
      (node (ref "C6") (pin "1") (pinfunction "P$1_1") (pintype "passive"))
      (node (ref "C7") (pin "1") (pinfunction "P$1_1") (pintype "passive"))
      (node (ref "FB2") (pin "2") (pinfunction "P$2_2") (pintype "passive"))
      (node (ref "LDO_VREG") (pin "VIN") (pinfunction "3_VIN") (pintype "bidirectional"))
      (node (ref "U$5") (pin "P$1") (pinfunction "1_P$1") (pintype "bidirectional"))
    )
    (net (code "42") (name "XTALIN") (class "Default")
      (node (ref "C14") (pin "2") (pinfunction "P$2_2") (pintype "passive"))
      (node (ref "IC") (pin "2") (pinfunction "XTAL1_2") (pintype "bidirectional"))
      (node (ref "XTAL_RF") (pin "1") (pinfunction "XIN_1") (pintype "bidirectional"))
    )
    (net (code "43") (name "XTALOUT") (class "Default")
      (node (ref "C15") (pin "1") (pinfunction "P$1_1") (pintype "passive"))
      (node (ref "IC") (pin "1") (pinfunction "XTAL2_1") (pintype "bidirectional"))
      (node (ref "XTAL_RF") (pin "3") (pinfunction "XOUT_3") (pintype "bidirectional"))
    )
    (net (code "44") (name "unconnected-(BARO-SDO-Pad6)") (class "Default")
      (node (ref "BARO") (pin "6") (pinfunction "SDO_6") (pintype "bidirectional"))
    )
    (net (code "45") (name "unconnected-(IMU-AD0{slash}SDO-PadP$9)") (class "Default")
      (node (ref "IMU") (pin "P$9") (pinfunction "AD0/SDO_P$9") (pintype "bidirectional"))
    )
    (net (code "46") (name "unconnected-(IMU-AUX_CL-PadP$7)") (class "Default")
      (node (ref "IMU") (pin "P$7") (pinfunction "AUX_CL_P$7") (pintype "bidirectional"))
    )
    (net (code "47") (name "unconnected-(IMU-AUX_DA-PadP$21)") (class "Default")
      (node (ref "IMU") (pin "P$21") (pinfunction "AUX_DA_P$21") (pintype "bidirectional"))
    )
    (net (code "48") (name "unconnected-(IMU-GND-PadP$18)") (class "Default")
      (node (ref "IMU") (pin "P$18") (pinfunction "GND_P$18") (pintype "bidirectional"))
    )
    (net (code "49") (name "unconnected-(IMU-NC-PadP$2)") (class "Default")
      (node (ref "IMU") (pin "P$2") (pinfunction "NC_P$2") (pintype "bidirectional"))
    )
    (net (code "50") (name "unconnected-(IMU-NC-PadP$3)") (class "Default")
      (node (ref "IMU") (pin "P$3") (pinfunction "NC_P$3") (pintype "bidirectional"))
    )
    (net (code "51") (name "unconnected-(IMU-NC-PadP$4)") (class "Default")
      (node (ref "IMU") (pin "P$4") (pinfunction "NC_P$4") (pintype "bidirectional"))
    )
    (net (code "52") (name "unconnected-(IMU-NC-PadP$5)") (class "Default")
      (node (ref "IMU") (pin "P$5") (pinfunction "NC_P$5") (pintype "bidirectional"))
    )
    (net (code "53") (name "unconnected-(IMU-NC-PadP$6)") (class "Default")
      (node (ref "IMU") (pin "P$6") (pinfunction "NC_P$6") (pintype "bidirectional"))
    )
    (net (code "54") (name "unconnected-(IMU-NC-PadP$14)") (class "Default")
      (node (ref "IMU") (pin "P$14") (pinfunction "NC_P$14") (pintype "bidirectional"))
    )
    (net (code "55") (name "unconnected-(IMU-NC-PadP$15)") (class "Default")
      (node (ref "IMU") (pin "P$15") (pinfunction "NC_P$15") (pintype "bidirectional"))
    )
    (net (code "56") (name "unconnected-(IMU-NC-PadP$16)") (class "Default")
      (node (ref "IMU") (pin "P$16") (pinfunction "NC_P$16") (pintype "bidirectional"))
    )
    (net (code "57") (name "unconnected-(IMU-NC-PadP$17)") (class "Default")
      (node (ref "IMU") (pin "P$17") (pinfunction "NC_P$17") (pintype "bidirectional"))
    )
    (net (code "58") (name "unconnected-(IMU-RESV-PadP$19)") (class "Default")
      (node (ref "IMU") (pin "P$19") (pinfunction "RESV_P$19") (pintype "bidirectional"))
    )
    (net (code "59") (name "unconnected-(U$12-2-PadNC1)") (class "Default")
      (node (ref "U$12") (pin "NC1") (pinfunction "2_NC1") (pintype "bidirectional"))
    )
    (net (code "60") (name "unconnected-(U$12-3-PadNC2)") (class "Default")
      (node (ref "U$12") (pin "NC2") (pinfunction "3_NC2") (pintype "bidirectional"))
    )
    (net (code "61") (name "unconnected-(U$12-4-PadNC3)") (class "Default")
      (node (ref "U$12") (pin "NC3") (pinfunction "4_NC3") (pintype "bidirectional"))
    )
  )
)
